# SoundMaker.net
KiCad netlist of a schematic drawn in EAGLE
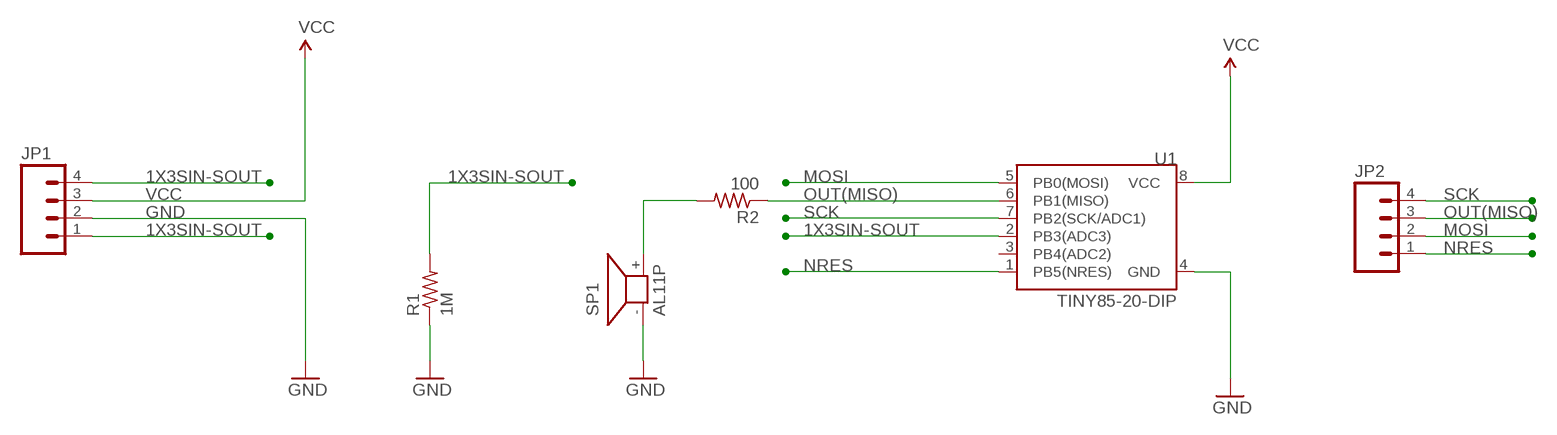
[diagram p0: schematic, sheet 1]

(export (version "E")
  (design (tool "Eeschema 10.0.6"))
  (components
    (comp (ref "JP1")
      (value "M04PTH")
      (footprint "eagle-import:1X04")
      (libsource (lib "eagle-import") (part "M04PTH"))
    )
    (comp (ref "JP2")
      (value "M04PTH")
      (footprint "eagle-import:1X04")
      (libsource (lib "eagle-import") (part "M04PTH"))
    )
    (comp (ref "R1")
      (value "1M")
      (footprint "eagle-import:R0603")
      (libsource (lib "eagle-import") (part "R-US_R0603"))
    )
    (comp (ref "R2")
      (value "100")
      (footprint "eagle-import:R0603")
      (libsource (lib "eagle-import") (part "R-US_R0603"))
    )
    (comp (ref "SP1")
      (value "AL11P")
      (footprint "eagle-import:AL11P")
      (libsource (lib "eagle-import") (part "AL11P"))
    )
    (comp (ref "U1")
      (value "TINY85-20-DIP")
      (footprint "eagle-import:DIP08")
      (libsource (lib "eagle-import") (part "ATTINY45TINY85-20-DIP"))
    )
  )
  (nets
    (net (code "1") (name "/1X3SIN-SOUT") (class "Default")
      (node (ref "JP1") (pin "1") (pinfunction "1_1") (pintype "passive"))
      (node (ref "JP1") (pin "4") (pinfunction "4_4") (pintype "passive"))
      (node (ref "R1") (pin "2") (pinfunction "2_2") (pintype "passive"))
      (node (ref "U1") (pin "2") (pinfunction "PB3(ADC3)_2") (pintype "bidirectional"))
    )
    (net (code "2") (name "/MOSI") (class "Default")
      (node (ref "JP2") (pin "2") (pinfunction "2_2") (pintype "passive"))
      (node (ref "U1") (pin "5") (pinfunction "PB0(MOSI)_5") (pintype "bidirectional"))
    )
    (net (code "3") (name "/NRES") (class "Default")
      (node (ref "JP2") (pin "1") (pinfunction "1_1") (pintype "passive"))
      (node (ref "U1") (pin "1") (pinfunction "PB5(NRES)_1") (pintype "bidirectional"))
    )
    (net (code "4") (name "/OUT(MISO)") (class "Default")
      (node (ref "JP2") (pin "3") (pinfunction "3_3") (pintype "passive"))
      (node (ref "R2") (pin "1") (pinfunction "1_1") (pintype "passive"))
      (node (ref "U1") (pin "6") (pinfunction "PB1(MISO)_6") (pintype "bidirectional"))
    )
    (net (code "5") (name "/SCK") (class "Default")
      (node (ref "JP2") (pin "4") (pinfunction "4_4") (pintype "passive"))
      (node (ref "U1") (pin "7") (pinfunction "PB2(SCK/ADC1)_7") (pintype "bidirectional"))
    )
    (net (code "6") (name "GND") (class "Default")
      (node (ref "JP1") (pin "2") (pinfunction "2_2") (pintype "passive"))
      (node (ref "R1") (pin "1") (pinfunction "1_1") (pintype "passive"))
      (node (ref "SP1") (pin "-") (pinfunction "1_-") (pintype "passive"))
      (node (ref "U1") (pin "4") (pinfunction "GND_4") (pintype "bidirectional"))
    )
    (net (code "7") (name "Net-(SP1-2)") (class "Default")
      (node (ref "R2") (pin "2") (pinfunction "2_2") (pintype "passive"))
      (node (ref "SP1") (pin "+") (pinfunction "2_+") (pintype "passive"))
    )
    (net (code "8") (name "VCC") (class "Default")
      (node (ref "JP1") (pin "3") (pinfunction "3_3") (pintype "passive"))
      (node (ref "U1") (pin "8") (pinfunction "VCC_8") (pintype "bidirectional"))
    )
    (net (code "9") (name "unconnected-(U1-PB4(ADC2)-Pad3)") (class "Default")
      (node (ref "U1") (pin "3") (pinfunction "PB4(ADC2)_3") (pintype "bidirectional"))
    )
  )
)
